# RFTranceiver.net
KiCad netlist of a schematic drawn in Altium Designer
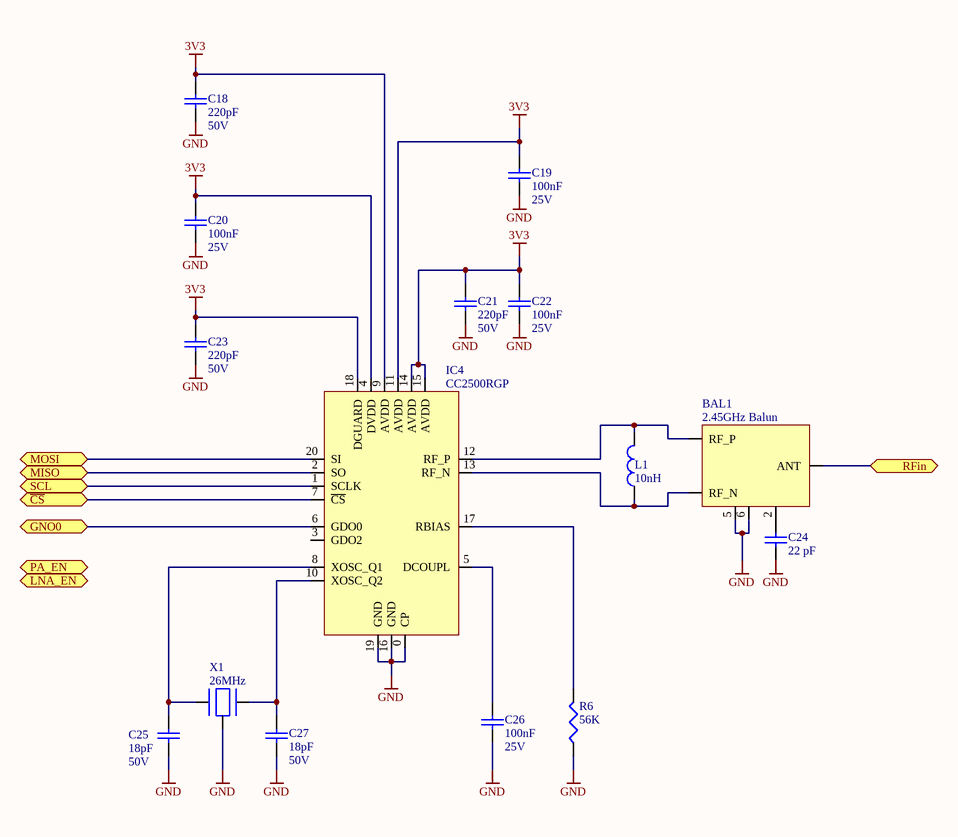
[diagram p0: RFTranceiver.SchDoc]

(export (version "E")
  (design (tool "Eeschema 10.0.6"))
  (components
    (comp (ref "BAL1")
      (value "2.45GHz Balun")
      (footprint "AgPt")
      (description "Signal Conditioning 2.45GHz BALUN/FILTER")
      (libsource (lib "AR_RF") (part "2450BM15B0003E"))
    )
    (comp (ref "C18")
      (value "220pF")
      (footprint "C0402")
      (description "Capacitor, 220pF, 50V, NP0")
      (fields (field (name "VOLTAGE RATING") "50V"))
      (libsource (lib "AR_Capacitors_Ceramic") (part "220pF/0402/CER/50V"))
    )
    (comp (ref "C19")
      (value "100nF")
      (footprint "C0402")
      (description "Capacitor, 100nF, 25V, X7R")
      (fields (field (name "VOLTAGE RATING") "25V"))
      (libsource (lib "AR_Capacitors_Ceramic") (part "100nF/0402/CER/25V"))
    )
    (comp (ref "C20")
      (value "100nF")
      (footprint "C0402")
      (description "Capacitor, 100nF, 25V, X7R")
      (fields (field (name "VOLTAGE RATING") "25V"))
      (libsource (lib "AR_Capacitors_Ceramic") (part "100nF/0402/CER/25V"))
    )
    (comp (ref "C21")
      (value "220pF")
      (footprint "C0402")
      (description "Capacitor, 220pF, 50V, NP0")
      (fields (field (name "VOLTAGE RATING") "50V"))
      (libsource (lib "AR_Capacitors_Ceramic") (part "220pF/0402/CER/50V"))
    )
    (comp (ref "C22")
      (value "100nF")
      (footprint "C0402")
      (description "Capacitor, 100nF, 25V, X7R")
      (fields (field (name "VOLTAGE RATING") "25V"))
      (libsource (lib "AR_Capacitors_Ceramic") (part "100nF/0402/CER/25V"))
    )
    (comp (ref "C23")
      (value "220pF")
      (footprint "C0402")
      (description "Capacitor, 220pF, 50V, NP0")
      (fields (field (name "VOLTAGE RATING") "50V"))
      (libsource (lib "AR_Capacitors_Ceramic") (part "220pF/0402/CER/50V"))
    )
    (comp (ref "C24")
      (value "22 pF")
      (footprint "C0402")
      (description "Capacitor, 22pF, 50V, NP0")
      (libsource (lib "AR_Capacitors_RF") (part "22pF/0402/NP0/50V"))
    )
    (comp (ref "C25")
      (value "18pF")
      (footprint "C0603")
      (description "Capacitor, 18pF, 50V, C0G / NP0")
      (fields (field (name "VOLTAGE RATING") "50V"))
      (libsource (lib "AR_Capacitors_Ceramic") (part "18pF/0603/CER/50V"))
    )
    (comp (ref "C26")
      (value "100nF")
      (footprint "C0402")
      (description "Capacitor, 100nF, 25V, X7R")
      (fields (field (name "VOLTAGE RATING") "25V"))
      (libsource (lib "AR_Capacitors_Ceramic") (part "100nF/0402/CER/25V"))
    )
    (comp (ref "C27")
      (value "18pF")
      (footprint "C0603")
      (description "Capacitor, 18pF, 50V, C0G / NP0")
      (fields (field (name "VOLTAGE RATING") "50V"))
      (libsource (lib "AR_Capacitors_Ceramic") (part "18pF/0603/CER/50V"))
    )
    (comp (ref "IC4")
      (value "CC2500RGP")
      (footprint "QFN20")
      (description "RF Transceiver Low-Power 2.4 GHz RF Transceiver")
      (libsource (lib "AR_ICs") (part "CC2500RGP"))
    )
    (comp (ref "L1")
      (value "10nH")
      (footprint "0402")
      (description "Inductor, 10nH, 250mAdc, 870ohm")
      (libsource (lib "AR_Inductors") (part "10nH-0403"))
    )
    (comp (ref "R6")
      (value "56K")
      (footprint "0402")
      (description "Resistor, 56k, 0.1%, 0.0625W, 50V, 100PPM, 0402")
      (libsource (lib "AR_Resistors_SMD") (part "56k/0402/0063W/50V"))
    )
    (comp (ref "X1")
      (value "26MHz")
      (footprint "7M")
      (description "CRYSTAL, 26MHz,18PF CL, 3.2X2.5MM SMT")
      (libsource (lib "AR_Crystals") (part "7M-26.000MAAJ-T"))
    )
  )
  (nets
    (net (code "1") (name "/GNO0") (class "Default")
      (node (ref "IC4") (pin "6") (pinfunction "GDO0_6") (pintype "passive"))
    )
    (net (code "3") (name "/MISO") (class "Default")
      (node (ref "IC4") (pin "2") (pinfunction "SO_2") (pintype "passive"))
    )
    (net (code "4") (name "/MOSI") (class "Default")
      (node (ref "IC4") (pin "20") (pinfunction "SI_20") (pintype "passive"))
    )
    (net (code "6") (name "/RFin") (class "Default")
      (node (ref "BAL1") (pin "1") (pinfunction "ANT_1") (pintype "power_in"))
    )
    (net (code "7") (name "/SCL") (class "Default")
      (node (ref "IC4") (pin "1") (pinfunction "SCLK_1") (pintype "passive"))
    )
    (net (code "8") (name "/~{CS}") (class "Default")
      (node (ref "IC4") (pin "7") (pinfunction "~{CS}_7") (pintype "passive"))
    )
    (net (code "9") (name "3V3") (class "Default")
      (node (ref "C18") (pin "2") (pinfunction "2_2") (pintype "passive"))
      (node (ref "C19") (pin "2") (pinfunction "2_2") (pintype "passive"))
      (node (ref "C20") (pin "2") (pinfunction "2_2") (pintype "passive"))
      (node (ref "C21") (pin "2") (pinfunction "2_2") (pintype "passive"))
      (node (ref "C22") (pin "2") (pinfunction "2_2") (pintype "passive"))
      (node (ref "C23") (pin "2") (pinfunction "2_2") (pintype "passive"))
      (node (ref "IC4") (pin "11") (pinfunction "AVDD_11") (pintype "power_in"))
      (node (ref "IC4") (pin "14") (pinfunction "AVDD_14") (pintype "power_in"))
      (node (ref "IC4") (pin "15") (pinfunction "AVDD_15") (pintype "power_in"))
      (node (ref "IC4") (pin "18") (pinfunction "DGUARD_18") (pintype "power_in"))
      (node (ref "IC4") (pin "4") (pinfunction "DVDD_4") (pintype "power_in"))
      (node (ref "IC4") (pin "9") (pinfunction "AVDD_9") (pintype "power_in"))
    )
    (net (code "10") (name "GND") (class "Default")
      (node (ref "BAL1") (pin "5") (pinfunction "GND_5") (pintype "power_in"))
      (node (ref "BAL1") (pin "6") (pinfunction "GND_6") (pintype "power_in"))
      (node (ref "C18") (pin "1") (pinfunction "1_1") (pintype "passive"))
      (node (ref "C19") (pin "1") (pinfunction "1_1") (pintype "passive"))
      (node (ref "C20") (pin "1") (pinfunction "1_1") (pintype "passive"))
      (node (ref "C21") (pin "1") (pinfunction "1_1") (pintype "passive"))
      (node (ref "C22") (pin "1") (pinfunction "1_1") (pintype "passive"))
      (node (ref "C23") (pin "1") (pinfunction "1_1") (pintype "passive"))
      (node (ref "C24") (pin "1") (pinfunction "1_1") (pintype "passive"))
      (node (ref "C25") (pin "1") (pinfunction "1_1") (pintype "passive"))
      (node (ref "C26") (pin "1") (pinfunction "1_1") (pintype "passive"))
      (node (ref "C27") (pin "1") (pinfunction "1_1") (pintype "passive"))
      (node (ref "IC4") (pin "0") (pinfunction "CP_0") (pintype "power_in"))
      (node (ref "IC4") (pin "16") (pinfunction "GND_16") (pintype "power_in"))
      (node (ref "IC4") (pin "19") (pinfunction "GND_19") (pintype "power_in"))
      (node (ref "R6") (pin "1") (pinfunction "1_1") (pintype "passive"))
      (node (ref "X1") (pin "0") (pinfunction "0_0") (pintype "power_in"))
    )
    (net (code "11") (name "Net-(BAL1-GND-Pad2)") (class "Default")
      (node (ref "BAL1") (pin "2") (pinfunction "GND_2") (pintype "power_in"))
      (node (ref "C24") (pin "2") (pinfunction "2_2") (pintype "passive"))
    )
    (net (code "12") (name "Net-(BAL1-RF_N)") (class "Default")
      (node (ref "BAL1") (pin "3") (pinfunction "RF_N_3") (pintype "power_in"))
      (node (ref "IC4") (pin "13") (pinfunction "RF_N_13") (pintype "passive"))
      (node (ref "L1") (pin "1") (pinfunction "1_1") (pintype "passive"))
    )
    (net (code "13") (name "Net-(BAL1-RF_P)") (class "Default")
      (node (ref "BAL1") (pin "4") (pinfunction "RF_P_4") (pintype "power_in"))
      (node (ref "IC4") (pin "12") (pinfunction "RF_P_12") (pintype "passive"))
      (node (ref "L1") (pin "2") (pinfunction "2_2") (pintype "passive"))
    )
    (net (code "14") (name "Net-(IC4-DCOUPL)") (class "Default")
      (node (ref "C26") (pin "2") (pinfunction "2_2") (pintype "passive"))
      (node (ref "IC4") (pin "5") (pinfunction "DCOUPL_5") (pintype "passive"))
    )
    (net (code "15") (name "Net-(IC4-RBIAS)") (class "Default")
      (node (ref "IC4") (pin "17") (pinfunction "RBIAS_17") (pintype "passive"))
      (node (ref "R6") (pin "2") (pinfunction "2_2") (pintype "passive"))
    )
    (net (code "16") (name "Net-(IC4-XOSC_Q1)") (class "Default")
      (node (ref "C25") (pin "2") (pinfunction "2_2") (pintype "passive"))
      (node (ref "IC4") (pin "8") (pinfunction "XOSC_Q1_8") (pintype "passive"))
      (node (ref "X1") (pin "1") (pinfunction "1_1") (pintype "passive"))
    )
    (net (code "17") (name "Net-(IC4-XOSC_Q2)") (class "Default")
      (node (ref "C27") (pin "2") (pinfunction "2_2") (pintype "passive"))
      (node (ref "IC4") (pin "10") (pinfunction "XOSC_Q2_10") (pintype "passive"))
      (node (ref "X1") (pin "2") (pinfunction "2_2") (pintype "passive"))
    )
    (net (code "18") (name "unconnected-(IC4-GDO2-Pad3)") (class "Default")
      (node (ref "IC4") (pin "3") (pinfunction "GDO2_3") (pintype "passive"))
    )
  )
)
